# Tickler-Brains_Brawn.net
KiCad netlist of a schematic drawn in EAGLE
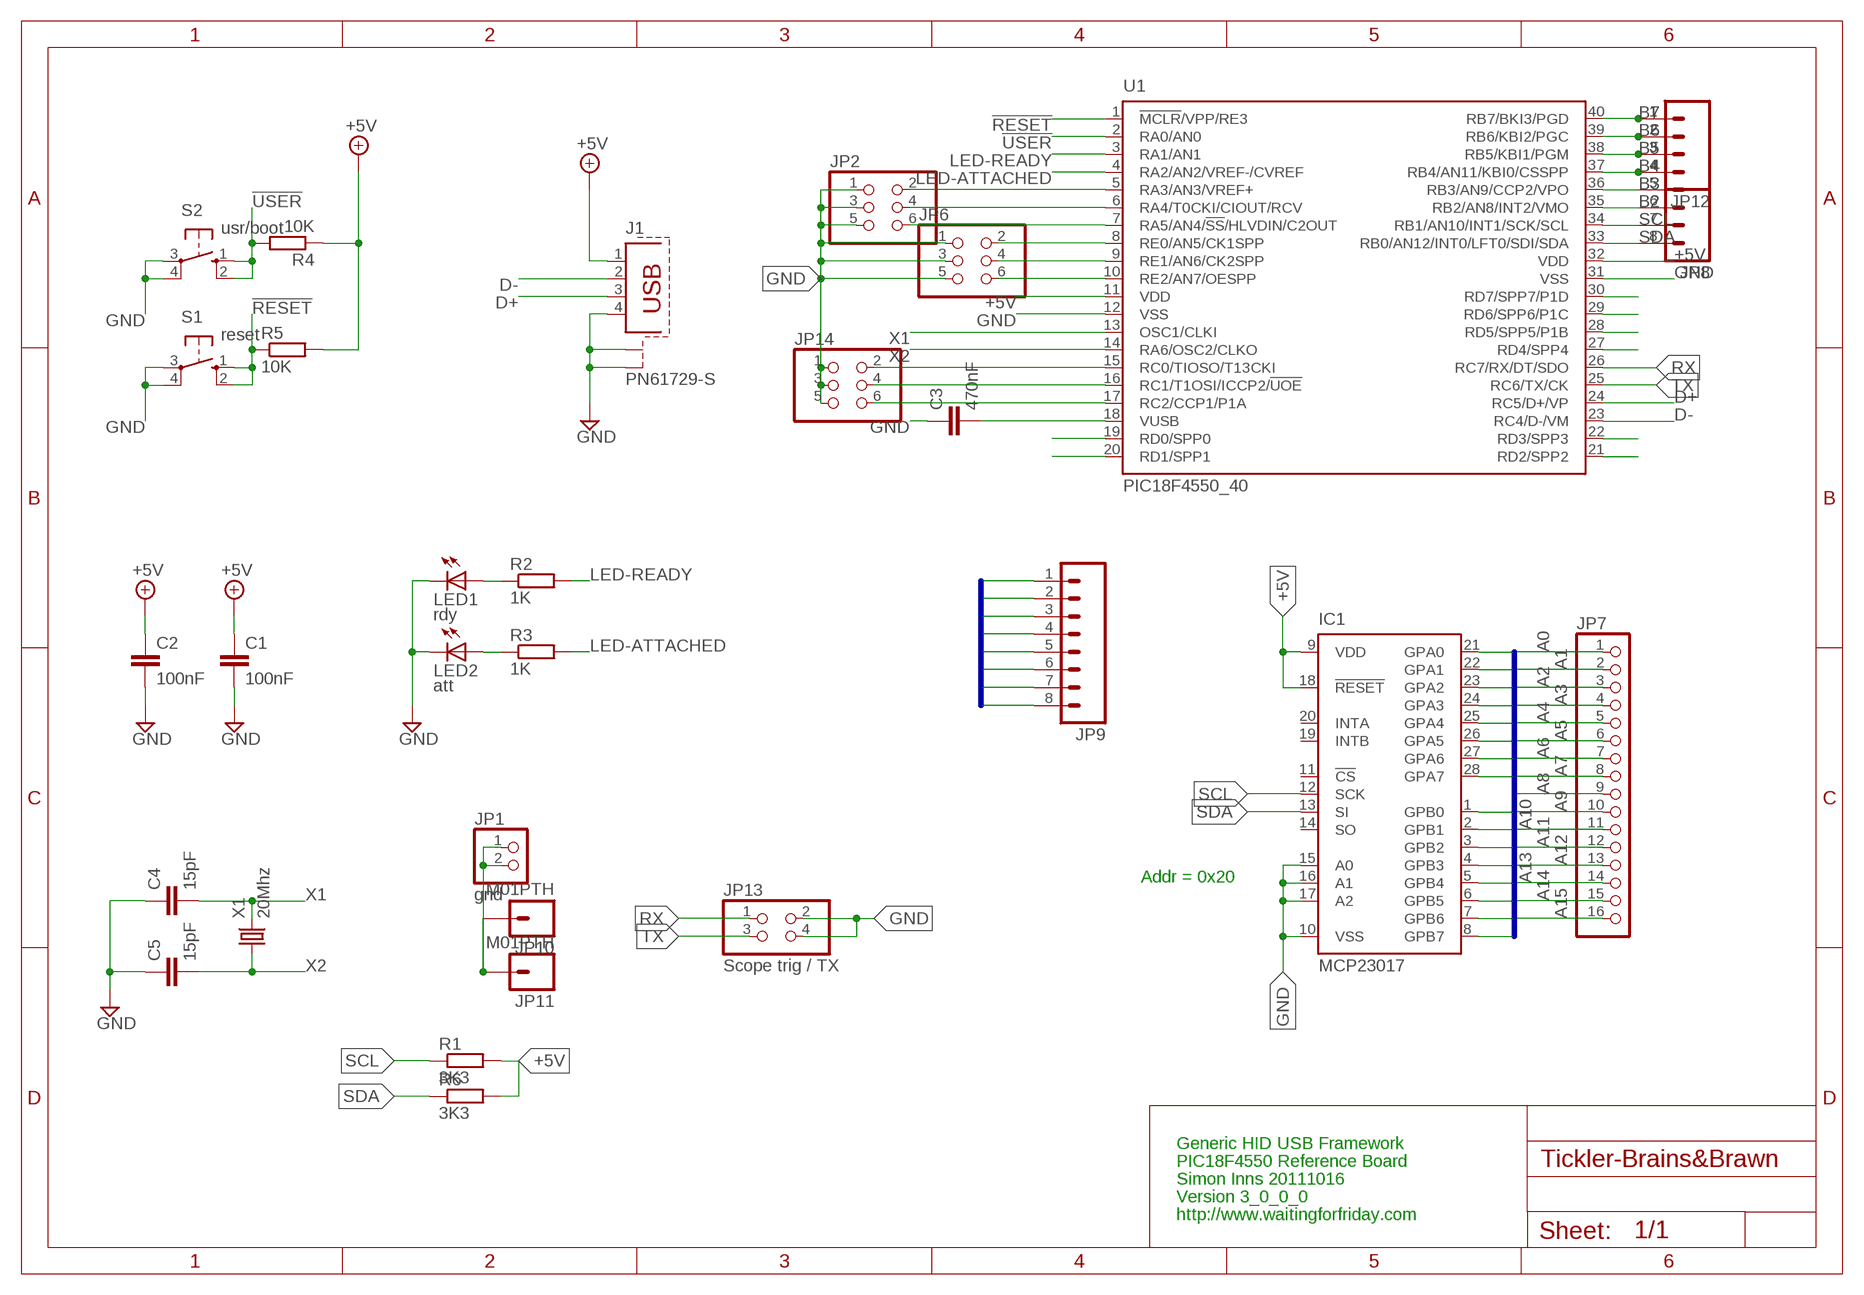
[diagram p0: schematic, sheet 1]

(export (version "E")
  (design (tool "Eeschema 10.0.6"))
  (components
    (comp (ref "C1")
      (value "100nF")
      (footprint "eagle-import:C025-025X050")
      (libsource (lib "eagle-import") (part "C-EU025-025X050"))
    )
    (comp (ref "C2")
      (value "100nF")
      (footprint "eagle-import:C025-025X050")
      (libsource (lib "eagle-import") (part "C-EU025-025X050"))
    )
    (comp (ref "C3")
      (value "470nF")
      (footprint "eagle-import:C025-025X050")
      (libsource (lib "eagle-import") (part "C-EU025-025X050"))
    )
    (comp (ref "C4")
      (value "15pF")
      (footprint "eagle-import:C050-024X044")
      (libsource (lib "eagle-import") (part "C-EU050-024X044"))
    )
    (comp (ref "C5")
      (value "15pF")
      (footprint "eagle-import:C050-024X044")
      (libsource (lib "eagle-import") (part "C-EU050-024X044"))
    )
    (comp (ref "IC1")
      (value "MCP23017")
      (footprint "eagle-import:DIL28-3")
      (fields (field (name "MF") "MICROCHIP") (field (name "MPN") "MCP23S17-E/SP"))
      (libsource (lib "eagle-import") (part "MCP23S17SP"))
    )
    (comp (ref "J1")
      (value "PN61729-S")
      (footprint "eagle-import:PN61729-S")
      (libsource (lib "eagle-import") (part "PN61729-S"))
    )
    (comp (ref "JP1")
      (value "gnd")
      (footprint "eagle-import:1X02")
      (libsource (lib "eagle-import") (part "PINHD-1X2"))
    )
    (comp (ref "JP2")
      (value "PINHD-2X3")
      (footprint "eagle-import:2X03")
      (libsource (lib "eagle-import") (part "PINHD-2X3"))
    )
    (comp (ref "JP6")
      (value "PINHD-2X3")
      (footprint "eagle-import:2X03")
      (libsource (lib "eagle-import") (part "PINHD-2X3"))
    )
    (comp (ref "JP7")
      (value "PINHD-1X16")
      (footprint "eagle-import:1X16")
      (libsource (lib "eagle-import") (part "PINHD-1X16"))
    )
    (comp (ref "JP8")
      (value "M08")
      (footprint "eagle-import:1X08")
      (libsource (lib "eagle-import") (part "M08"))
    )
    (comp (ref "JP9")
      (value "M08")
      (footprint "eagle-import:1X08")
      (libsource (lib "eagle-import") (part "M08"))
    )
    (comp (ref "JP10")
      (value "M01PTH")
      (footprint "eagle-import:1X01")
      (libsource (lib "eagle-import") (part "M01PTH"))
    )
    (comp (ref "JP11")
      (value "M01PTH")
      (footprint "eagle-import:1X01")
      (libsource (lib "eagle-import") (part "M01PTH"))
    )
    (comp (ref "JP12")
      (value "M04PTH")
      (footprint "eagle-import:1X04")
      (libsource (lib "eagle-import") (part "M04PTH"))
    )
    (comp (ref "JP13")
      (value "Scope trig / TX")
      (footprint "eagle-import:2X02")
      (libsource (lib "eagle-import") (part "PINHD-2X2"))
    )
    (comp (ref "JP14")
      (value "PINHD-2X3")
      (footprint "eagle-import:2X03")
      (libsource (lib "eagle-import") (part "PINHD-2X3"))
    )
    (comp (ref "LED1")
      (value "rdy")
      (footprint "eagle-import:LED3MM")
      (libsource (lib "eagle-import") (part "LED3MM"))
    )
    (comp (ref "LED2")
      (value "att")
      (footprint "eagle-import:LED3MM")
      (libsource (lib "eagle-import") (part "LED3MM"))
    )
    (comp (ref "R1")
      (value "3K3")
      (footprint "eagle-import:0207_10")
      (libsource (lib "eagle-import") (part "R-EU_0207/10"))
    )
    (comp (ref "R2")
      (value "1K")
      (footprint "eagle-import:0207_10")
      (libsource (lib "eagle-import") (part "R-EU_0207/10"))
    )
    (comp (ref "R3")
      (value "1K")
      (footprint "eagle-import:0207_10")
      (libsource (lib "eagle-import") (part "R-EU_0207/10"))
    )
    (comp (ref "R4")
      (value "10K")
      (footprint "eagle-import:0207_10")
      (libsource (lib "eagle-import") (part "R-EU_0207/10"))
    )
    (comp (ref "R5")
      (value "10K")
      (footprint "eagle-import:0207_10")
      (libsource (lib "eagle-import") (part "R-EU_0207/10"))
    )
    (comp (ref "R6")
      (value "3K3")
      (footprint "eagle-import:0207_10")
      (libsource (lib "eagle-import") (part "R-EU_0207/10"))
    )
    (comp (ref "S1")
      (value "reset")
      (footprint "eagle-import:B3F-10XX")
      (fields (field (name "MPN") "B3F-1000"))
      (libsource (lib "eagle-import") (part "10-XX"))
    )
    (comp (ref "S2")
      (value "usr/boot")
      (footprint "eagle-import:B3F-10XX")
      (fields (field (name "MPN") "B3F-1000"))
      (libsource (lib "eagle-import") (part "10-XX"))
    )
    (comp (ref "U1")
      (value "PIC18F4550_40")
      (footprint "eagle-import:DIL40")
      (fields (field (name "MF") "MICROCHIP") (field (name "MPN") "PIC18F4550-I/P"))
      (libsource (lib "eagle-import") (part "PIC18F4_40550"))
    )
    (comp (ref "X1")
      (value "20Mhz")
      (footprint "eagle-import:HC49U-V")
      (libsource (lib "eagle-import") (part "CRYSTALHC49U-V"))
    )
  )
  (nets
    (net (code "1") (name "+5V") (class "Default")
      (node (ref "C1") (pin "1") (pinfunction "1_1") (pintype "passive"))
      (node (ref "C2") (pin "1") (pinfunction "1_1") (pintype "passive"))
      (node (ref "IC1") (pin "18") (pinfunction "~{RESET}_18") (pintype "input"))
      (node (ref "IC1") (pin "9") (pinfunction "VDD_9") (pintype "power_in"))
      (node (ref "J1") (pin "1") (pinfunction "1_1") (pintype "passive"))
      (node (ref "R1") (pin "2") (pinfunction "2_2") (pintype "passive"))
      (node (ref "R4") (pin "1") (pinfunction "1_1") (pintype "passive"))
      (node (ref "R5") (pin "2") (pinfunction "2_2") (pintype "passive"))
      (node (ref "R6") (pin "2") (pinfunction "2_2") (pintype "passive"))
      (node (ref "U1") (pin "11") (pinfunction "VDD_11") (pintype "power_in"))
      (node (ref "U1") (pin "32") (pinfunction "VDD_32") (pintype "power_in"))
    )
    (net (code "2") (name "/A0") (class "Default")
      (node (ref "IC1") (pin "8") (pinfunction "GPB7_8") (pintype "bidirectional"))
      (node (ref "JP7") (pin "1") (pinfunction "1_1") (pintype "passive"))
    )
    (net (code "3") (name "/A1") (class "Default")
      (node (ref "IC1") (pin "21") (pinfunction "GPA0_21") (pintype "bidirectional"))
      (node (ref "JP7") (pin "2") (pinfunction "2_2") (pintype "passive"))
    )
    (net (code "4") (name "/A2") (class "Default")
      (node (ref "IC1") (pin "7") (pinfunction "GPB6_7") (pintype "bidirectional"))
      (node (ref "JP7") (pin "3") (pinfunction "3_3") (pintype "passive"))
    )
    (net (code "5") (name "/A3") (class "Default")
      (node (ref "IC1") (pin "22") (pinfunction "GPA1_22") (pintype "bidirectional"))
      (node (ref "JP7") (pin "4") (pinfunction "4_4") (pintype "passive"))
    )
    (net (code "6") (name "/A4") (class "Default")
      (node (ref "IC1") (pin "6") (pinfunction "GPB5_6") (pintype "bidirectional"))
      (node (ref "JP7") (pin "5") (pinfunction "5_5") (pintype "passive"))
    )
    (net (code "7") (name "/A5") (class "Default")
      (node (ref "IC1") (pin "23") (pinfunction "GPA2_23") (pintype "bidirectional"))
      (node (ref "JP7") (pin "6") (pinfunction "6_6") (pintype "passive"))
    )
    (net (code "8") (name "/A6") (class "Default")
      (node (ref "IC1") (pin "5") (pinfunction "GPB4_5") (pintype "bidirectional"))
      (node (ref "JP7") (pin "7") (pinfunction "7_7") (pintype "passive"))
    )
    (net (code "9") (name "/A7") (class "Default")
      (node (ref "IC1") (pin "24") (pinfunction "GPA3_24") (pintype "bidirectional"))
      (node (ref "JP7") (pin "8") (pinfunction "8_8") (pintype "passive"))
    )
    (net (code "10") (name "/A8") (class "Default")
      (node (ref "IC1") (pin "4") (pinfunction "GPB3_4") (pintype "bidirectional"))
      (node (ref "JP7") (pin "9") (pinfunction "9_9") (pintype "passive"))
    )
    (net (code "11") (name "/A9") (class "Default")
      (node (ref "IC1") (pin "25") (pinfunction "GPA4_25") (pintype "bidirectional"))
      (node (ref "JP7") (pin "10") (pinfunction "10_10") (pintype "passive"))
    )
    (net (code "12") (name "/A10") (class "Default")
      (node (ref "IC1") (pin "3") (pinfunction "GPB2_3") (pintype "bidirectional"))
      (node (ref "JP7") (pin "11") (pinfunction "11_11") (pintype "passive"))
    )
    (net (code "13") (name "/A11") (class "Default")
      (node (ref "IC1") (pin "26") (pinfunction "GPA5_26") (pintype "bidirectional"))
      (node (ref "JP7") (pin "12") (pinfunction "12_12") (pintype "passive"))
    )
    (net (code "14") (name "/A12") (class "Default")
      (node (ref "IC1") (pin "2") (pinfunction "GPB1_2") (pintype "bidirectional"))
      (node (ref "JP7") (pin "13") (pinfunction "13_13") (pintype "passive"))
    )
    (net (code "15") (name "/A13") (class "Default")
      (node (ref "IC1") (pin "27") (pinfunction "GPA6_27") (pintype "bidirectional"))
      (node (ref "JP7") (pin "14") (pinfunction "14_14") (pintype "passive"))
    )
    (net (code "16") (name "/A14") (class "Default")
      (node (ref "IC1") (pin "1") (pinfunction "GPB0_1") (pintype "bidirectional"))
      (node (ref "JP7") (pin "15") (pinfunction "15_15") (pintype "passive"))
    )
    (net (code "17") (name "/A15") (class "Default")
      (node (ref "IC1") (pin "28") (pinfunction "GPA7_28") (pintype "bidirectional"))
      (node (ref "JP7") (pin "16") (pinfunction "16_16") (pintype "passive"))
    )
    (net (code "18") (name "/B2") (class "Default")
      (node (ref "JP8") (pin "6") (pinfunction "6_6") (pintype "passive"))
      (node (ref "U1") (pin "35") (pinfunction "RB2/AN8/INT2/VMO_35") (pintype "bidirectional"))
    )
    (net (code "19") (name "/B3") (class "Default")
      (node (ref "JP8") (pin "5") (pinfunction "5_5") (pintype "passive"))
      (node (ref "U1") (pin "36") (pinfunction "RB3/AN9/CCP2/VPO_36") (pintype "bidirectional"))
    )
    (net (code "20") (name "/B4") (class "Default")
      (node (ref "JP12") (pin "4") (pinfunction "4_4") (pintype "passive"))
      (node (ref "JP8") (pin "4") (pinfunction "4_4") (pintype "passive"))
      (node (ref "U1") (pin "37") (pinfunction "RB4/AN11/KBI0/CSSPP_37") (pintype "bidirectional"))
    )
    (net (code "21") (name "/B5") (class "Default")
      (node (ref "JP12") (pin "3") (pinfunction "3_3") (pintype "passive"))
      (node (ref "JP8") (pin "3") (pinfunction "3_3") (pintype "passive"))
      (node (ref "U1") (pin "38") (pinfunction "RB5/KBI1/PGM_38") (pintype "bidirectional"))
    )
    (net (code "22") (name "/B6") (class "Default")
      (node (ref "JP12") (pin "2") (pinfunction "2_2") (pintype "passive"))
      (node (ref "JP8") (pin "2") (pinfunction "2_2") (pintype "passive"))
      (node (ref "U1") (pin "39") (pinfunction "RB6/KBI2/PGC_39") (pintype "bidirectional"))
    )
    (net (code "23") (name "/B7") (class "Default")
      (node (ref "JP12") (pin "1") (pinfunction "1_1") (pintype "passive"))
      (node (ref "JP8") (pin "1") (pinfunction "1_1") (pintype "passive"))
      (node (ref "U1") (pin "40") (pinfunction "RB7/BKI3/PGD_40") (pintype "bidirectional"))
    )
    (net (code "24") (name "/D+") (class "Default")
      (node (ref "J1") (pin "3") (pinfunction "3_3") (pintype "passive"))
      (node (ref "U1") (pin "24") (pinfunction "RC5/D+/VP_24") (pintype "bidirectional"))
    )
    (net (code "25") (name "/D-") (class "Default")
      (node (ref "J1") (pin "2") (pinfunction "2_2") (pintype "passive"))
      (node (ref "U1") (pin "23") (pinfunction "RC4/D-/VM_23") (pintype "bidirectional"))
    )
    (net (code "26") (name "/D0") (class "Default")
      (node (ref "JP9") (pin "1") (pinfunction "1_1") (pintype "passive"))
      (node (ref "U1") (pin "19") (pinfunction "RD0/SPP0_19") (pintype "bidirectional"))
    )
    (net (code "27") (name "/D1") (class "Default")
      (node (ref "JP9") (pin "2") (pinfunction "2_2") (pintype "passive"))
      (node (ref "U1") (pin "20") (pinfunction "RD1/SPP1_20") (pintype "bidirectional"))
    )
    (net (code "28") (name "/D2") (class "Default")
      (node (ref "JP9") (pin "3") (pinfunction "3_3") (pintype "passive"))
      (node (ref "U1") (pin "21") (pinfunction "RD2/SPP2_21") (pintype "bidirectional"))
    )
    (net (code "29") (name "/D3") (class "Default")
      (node (ref "JP9") (pin "4") (pinfunction "4_4") (pintype "passive"))
      (node (ref "U1") (pin "22") (pinfunction "RD3/SPP3_22") (pintype "bidirectional"))
    )
    (net (code "30") (name "/D4") (class "Default")
      (node (ref "JP9") (pin "5") (pinfunction "5_5") (pintype "passive"))
      (node (ref "U1") (pin "27") (pinfunction "RD4/SPP4_27") (pintype "bidirectional"))
    )
    (net (code "31") (name "/D5") (class "Default")
      (node (ref "JP9") (pin "6") (pinfunction "6_6") (pintype "passive"))
      (node (ref "U1") (pin "28") (pinfunction "RD5/SPP5/P1B_28") (pintype "bidirectional"))
    )
    (net (code "32") (name "/D6") (class "Default")
      (node (ref "JP9") (pin "7") (pinfunction "7_7") (pintype "passive"))
      (node (ref "U1") (pin "29") (pinfunction "RD6/SPP6/P1C_29") (pintype "bidirectional"))
    )
    (net (code "33") (name "/D7") (class "Default")
      (node (ref "JP9") (pin "8") (pinfunction "8_8") (pintype "passive"))
      (node (ref "U1") (pin "30") (pinfunction "RD7/SPP7/P1D_30") (pintype "bidirectional"))
    )
    (net (code "34") (name "/LED-ATTACHED") (class "Default")
      (node (ref "R3") (pin "2") (pinfunction "2_2") (pintype "passive"))
      (node (ref "U1") (pin "4") (pinfunction "RA2/AN2/VREF-/CVREF_4") (pintype "bidirectional"))
    )
    (net (code "35") (name "/LED-READY") (class "Default")
      (node (ref "R2") (pin "2") (pinfunction "2_2") (pintype "passive"))
      (node (ref "U1") (pin "3") (pinfunction "RA1/AN1_3") (pintype "bidirectional"))
    )
    (net (code "36") (name "/X1") (class "Default")
      (node (ref "C4") (pin "2") (pinfunction "2_2") (pintype "passive"))
      (node (ref "U1") (pin "13") (pinfunction "OSC1/CLKI_13") (pintype "input"))
      (node (ref "X1") (pin "2") (pinfunction "2_2") (pintype "passive"))
    )
    (net (code "37") (name "/X2") (class "Default")
      (node (ref "C5") (pin "2") (pinfunction "2_2") (pintype "passive"))
      (node (ref "U1") (pin "14") (pinfunction "RA6/OSC2/CLKO_14") (pintype "output"))
      (node (ref "X1") (pin "1") (pinfunction "1_1") (pintype "passive"))
    )
    (net (code "38") (name "/~{RESET}") (class "Default")
      (node (ref "R5") (pin "1") (pinfunction "1_1") (pintype "passive"))
      (node (ref "S1") (pin "1") (pinfunction "S_1") (pintype "passive"))
      (node (ref "S1") (pin "2") (pinfunction "S1_2") (pintype "passive"))
      (node (ref "U1") (pin "1") (pinfunction "~{MCLR}/VPP/RE3_1") (pintype "input"))
    )
    (net (code "39") (name "/~{USER}") (class "Default")
      (node (ref "R4") (pin "2") (pinfunction "2_2") (pintype "passive"))
      (node (ref "S2") (pin "1") (pinfunction "S_1") (pintype "passive"))
      (node (ref "S2") (pin "2") (pinfunction "S1_2") (pintype "passive"))
      (node (ref "U1") (pin "2") (pinfunction "RA0/AN0_2") (pintype "bidirectional"))
    )
    (net (code "40") (name "GND") (class "Default")
      (node (ref "C1") (pin "2") (pinfunction "2_2") (pintype "passive"))
      (node (ref "C2") (pin "2") (pinfunction "2_2") (pintype "passive"))
      (node (ref "C3") (pin "1") (pinfunction "1_1") (pintype "passive"))
      (node (ref "C4") (pin "1") (pinfunction "1_1") (pintype "passive"))
      (node (ref "C5") (pin "1") (pinfunction "1_1") (pintype "passive"))
      (node (ref "IC1") (pin "10") (pinfunction "VSS_10") (pintype "power_in"))
      (node (ref "IC1") (pin "15") (pinfunction "A0_15") (pintype "input"))
      (node (ref "IC1") (pin "16") (pinfunction "A1_16") (pintype "input"))
      (node (ref "IC1") (pin "17") (pinfunction "A2_17") (pintype "input"))
      (node (ref "J1") (pin "4") (pinfunction "4_4") (pintype "passive"))
      (node (ref "J1") (pin "S1") (pinfunction "S1_S1") (pintype "passive"))
      (node (ref "J1") (pin "S2") (pinfunction "S2_S2") (pintype "passive"))
      (node (ref "JP1") (pin "1") (pinfunction "1_1") (pintype "passive"))
      (node (ref "JP1") (pin "2") (pinfunction "2_2") (pintype "passive"))
      (node (ref "JP10") (pin "1") (pinfunction "1_1") (pintype "passive"))
      (node (ref "JP11") (pin "1") (pinfunction "1_1") (pintype "passive"))
      (node (ref "JP13") (pin "2") (pinfunction "2_2") (pintype "passive"))
      (node (ref "JP13") (pin "4") (pinfunction "4_4") (pintype "passive"))
      (node (ref "JP14") (pin "1") (pinfunction "1_1") (pintype "passive"))
      (node (ref "JP14") (pin "3") (pinfunction "3_3") (pintype "passive"))
      (node (ref "JP14") (pin "5") (pinfunction "5_5") (pintype "passive"))
      (node (ref "JP2") (pin "1") (pinfunction "1_1") (pintype "passive"))
      (node (ref "JP2") (pin "3") (pinfunction "3_3") (pintype "passive"))
      (node (ref "JP2") (pin "5") (pinfunction "5_5") (pintype "passive"))
      (node (ref "JP6") (pin "1") (pinfunction "1_1") (pintype "passive"))
      (node (ref "JP6") (pin "3") (pinfunction "3_3") (pintype "passive"))
      (node (ref "JP6") (pin "5") (pinfunction "5_5") (pintype "passive"))
      (node (ref "LED1") (pin "K") (pinfunction "C_K") (pintype "passive"))
      (node (ref "LED2") (pin "K") (pinfunction "C_K") (pintype "passive"))
      (node (ref "S1") (pin "3") (pinfunction "P_3") (pintype "passive"))
      (node (ref "S1") (pin "4") (pinfunction "P1_4") (pintype "passive"))
      (node (ref "S2") (pin "3") (pinfunction "P_3") (pintype "passive"))
      (node (ref "S2") (pin "4") (pinfunction "P1_4") (pintype "passive"))
      (node (ref "U1") (pin "12") (pinfunction "VSS_12") (pintype "power_in"))
      (node (ref "U1") (pin "31") (pinfunction "VSS_31") (pintype "power_in"))
    )
    (net (code "41") (name "Net-(LED1-PadA)") (class "Default")
      (node (ref "LED1") (pin "A") (pinfunction "A_A") (pintype "passive"))
      (node (ref "R2") (pin "1") (pinfunction "1_1") (pintype "passive"))
    )
    (net (code "42") (name "Net-(LED2-PadA)") (class "Default")
      (node (ref "LED2") (pin "A") (pinfunction "A_A") (pintype "passive"))
      (node (ref "R3") (pin "1") (pinfunction "1_1") (pintype "passive"))
    )
    (net (code "43") (name "Net-(U1-RA3{slash}AN3{slash}VREF+)") (class "Default")
      (node (ref "JP2") (pin "2") (pinfunction "2_2") (pintype "passive"))
      (node (ref "U1") (pin "5") (pinfunction "RA3/AN3/VREF+_5") (pintype "bidirectional"))
    )
    (net (code "44") (name "Net-(U1-RA4{slash}T0CKI{slash}CIOUT{slash}RCV)") (class "Default")
      (node (ref "JP2") (pin "4") (pinfunction "4_4") (pintype "passive"))
      (node (ref "U1") (pin "6") (pinfunction "RA4/T0CKI/CIOUT/RCV_6") (pintype "bidirectional"))
    )
    (net (code "45") (name "Net-(U1-RA5{slash}AN4{slash}~{SS}{slash}HLVDIN{slash}C2OUT)") (class "Default")
      (node (ref "JP2") (pin "6") (pinfunction "6_6") (pintype "passive"))
      (node (ref "U1") (pin "7") (pinfunction "RA5/AN4/~{SS}/HLVDIN/C2OUT_7") (pintype "bidirectional"))
    )
    (net (code "46") (name "Net-(U1-RC0{slash}TIOSO{slash}T13CKI)") (class "Default")
      (node (ref "JP14") (pin "2") (pinfunction "2_2") (pintype "passive"))
      (node (ref "U1") (pin "15") (pinfunction "RC0/TIOSO/T13CKI_15") (pintype "bidirectional"))
    )
    (net (code "47") (name "Net-(U1-RC1{slash}T1OSI{slash}ICCP2{slash}~{UOE})") (class "Default")
      (node (ref "JP14") (pin "4") (pinfunction "4_4") (pintype "passive"))
      (node (ref "U1") (pin "16") (pinfunction "RC1/T1OSI/ICCP2/~{UOE}_16") (pintype "bidirectional"))
    )
    (net (code "48") (name "Net-(U1-RC2{slash}CCP1{slash}P1A)") (class "Default")
      (node (ref "JP14") (pin "6") (pinfunction "6_6") (pintype "passive"))
      (node (ref "U1") (pin "17") (pinfunction "RC2/CCP1/P1A_17") (pintype "bidirectional"))
    )
    (net (code "49") (name "Net-(U1-RE0{slash}AN5{slash}CK1SPP)") (class "Default")
      (node (ref "JP6") (pin "2") (pinfunction "2_2") (pintype "passive"))
      (node (ref "U1") (pin "8") (pinfunction "RE0/AN5/CK1SPP_8") (pintype "bidirectional"))
    )
    (net (code "50") (name "Net-(U1-RE1{slash}AN6{slash}CK2SPP)") (class "Default")
      (node (ref "JP6") (pin "4") (pinfunction "4_4") (pintype "passive"))
      (node (ref "U1") (pin "9") (pinfunction "RE1/AN6/CK2SPP_9") (pintype "bidirectional"))
    )
    (net (code "51") (name "Net-(U1-RE2{slash}AN7{slash}OESPP)") (class "Default")
      (node (ref "JP6") (pin "6") (pinfunction "6_6") (pintype "passive"))
      (node (ref "U1") (pin "10") (pinfunction "RE2/AN7/OESPP_10") (pintype "bidirectional"))
    )
    (net (code "52") (name "Net-(U1-VUSB)") (class "Default")
      (node (ref "C3") (pin "2") (pinfunction "2_2") (pintype "passive"))
      (node (ref "U1") (pin "18") (pinfunction "VUSB_18") (pintype "bidirectional"))
    )
    (net (code "53") (name "RX") (class "Default")
      (node (ref "JP13") (pin "1") (pinfunction "1_1") (pintype "passive"))
      (node (ref "U1") (pin "26") (pinfunction "RC7/RX/DT/SDO_26") (pintype "bidirectional"))
    )
    (net (code "54") (name "SCL") (class "Default")
      (node (ref "IC1") (pin "12") (pinfunction "SCK_12") (pintype "input"))
      (node (ref "JP8") (pin "7") (pinfunction "7_7") (pintype "passive"))
      (node (ref "R1") (pin "1") (pinfunction "1_1") (pintype "passive"))
      (node (ref "U1") (pin "34") (pinfunction "RB1/AN10/INT1/SCK/SCL_34") (pintype "bidirectional"))
    )
    (net (code "55") (name "SDA") (class "Default")
      (node (ref "IC1") (pin "13") (pinfunction "SI_13") (pintype "input"))
      (node (ref "JP8") (pin "8") (pinfunction "8_8") (pintype "passive"))
      (node (ref "R6") (pin "1") (pinfunction "1_1") (pintype "passive"))
      (node (ref "U1") (pin "33") (pinfunction "RB0/AN12/INT0/LFT0/SDI/SDA_33") (pintype "bidirectional"))
    )
    (net (code "56") (name "TX") (class "Default")
      (node (ref "JP13") (pin "3") (pinfunction "3_3") (pintype "passive"))
      (node (ref "U1") (pin "25") (pinfunction "RC6/TX/CK_25") (pintype "bidirectional"))
    )
    (net (code "57") (name "unconnected-(IC1-INTA-Pad20)") (class "Default")
      (node (ref "IC1") (pin "20") (pinfunction "INTA_20") (pintype "output"))
    )
    (net (code "58") (name "unconnected-(IC1-INTB-Pad19)") (class "Default")
      (node (ref "IC1") (pin "19") (pinfunction "INTB_19") (pintype "output"))
    )
    (net (code "59") (name "unconnected-(IC1-SO-Pad14)") (class "Default")
      (node (ref "IC1") (pin "14") (pinfunction "SO_14") (pintype "output"))
    )
    (net (code "60") (name "unconnected-(IC1-~{CS}-Pad11)") (class "Default")
      (node (ref "IC1") (pin "11") (pinfunction "~{CS}_11") (pintype "input"))
    )
  )
)
